# ETH1G_RGMII_RTL8211F.net
KiCad netlist of a schematic drawn in Altium Designer
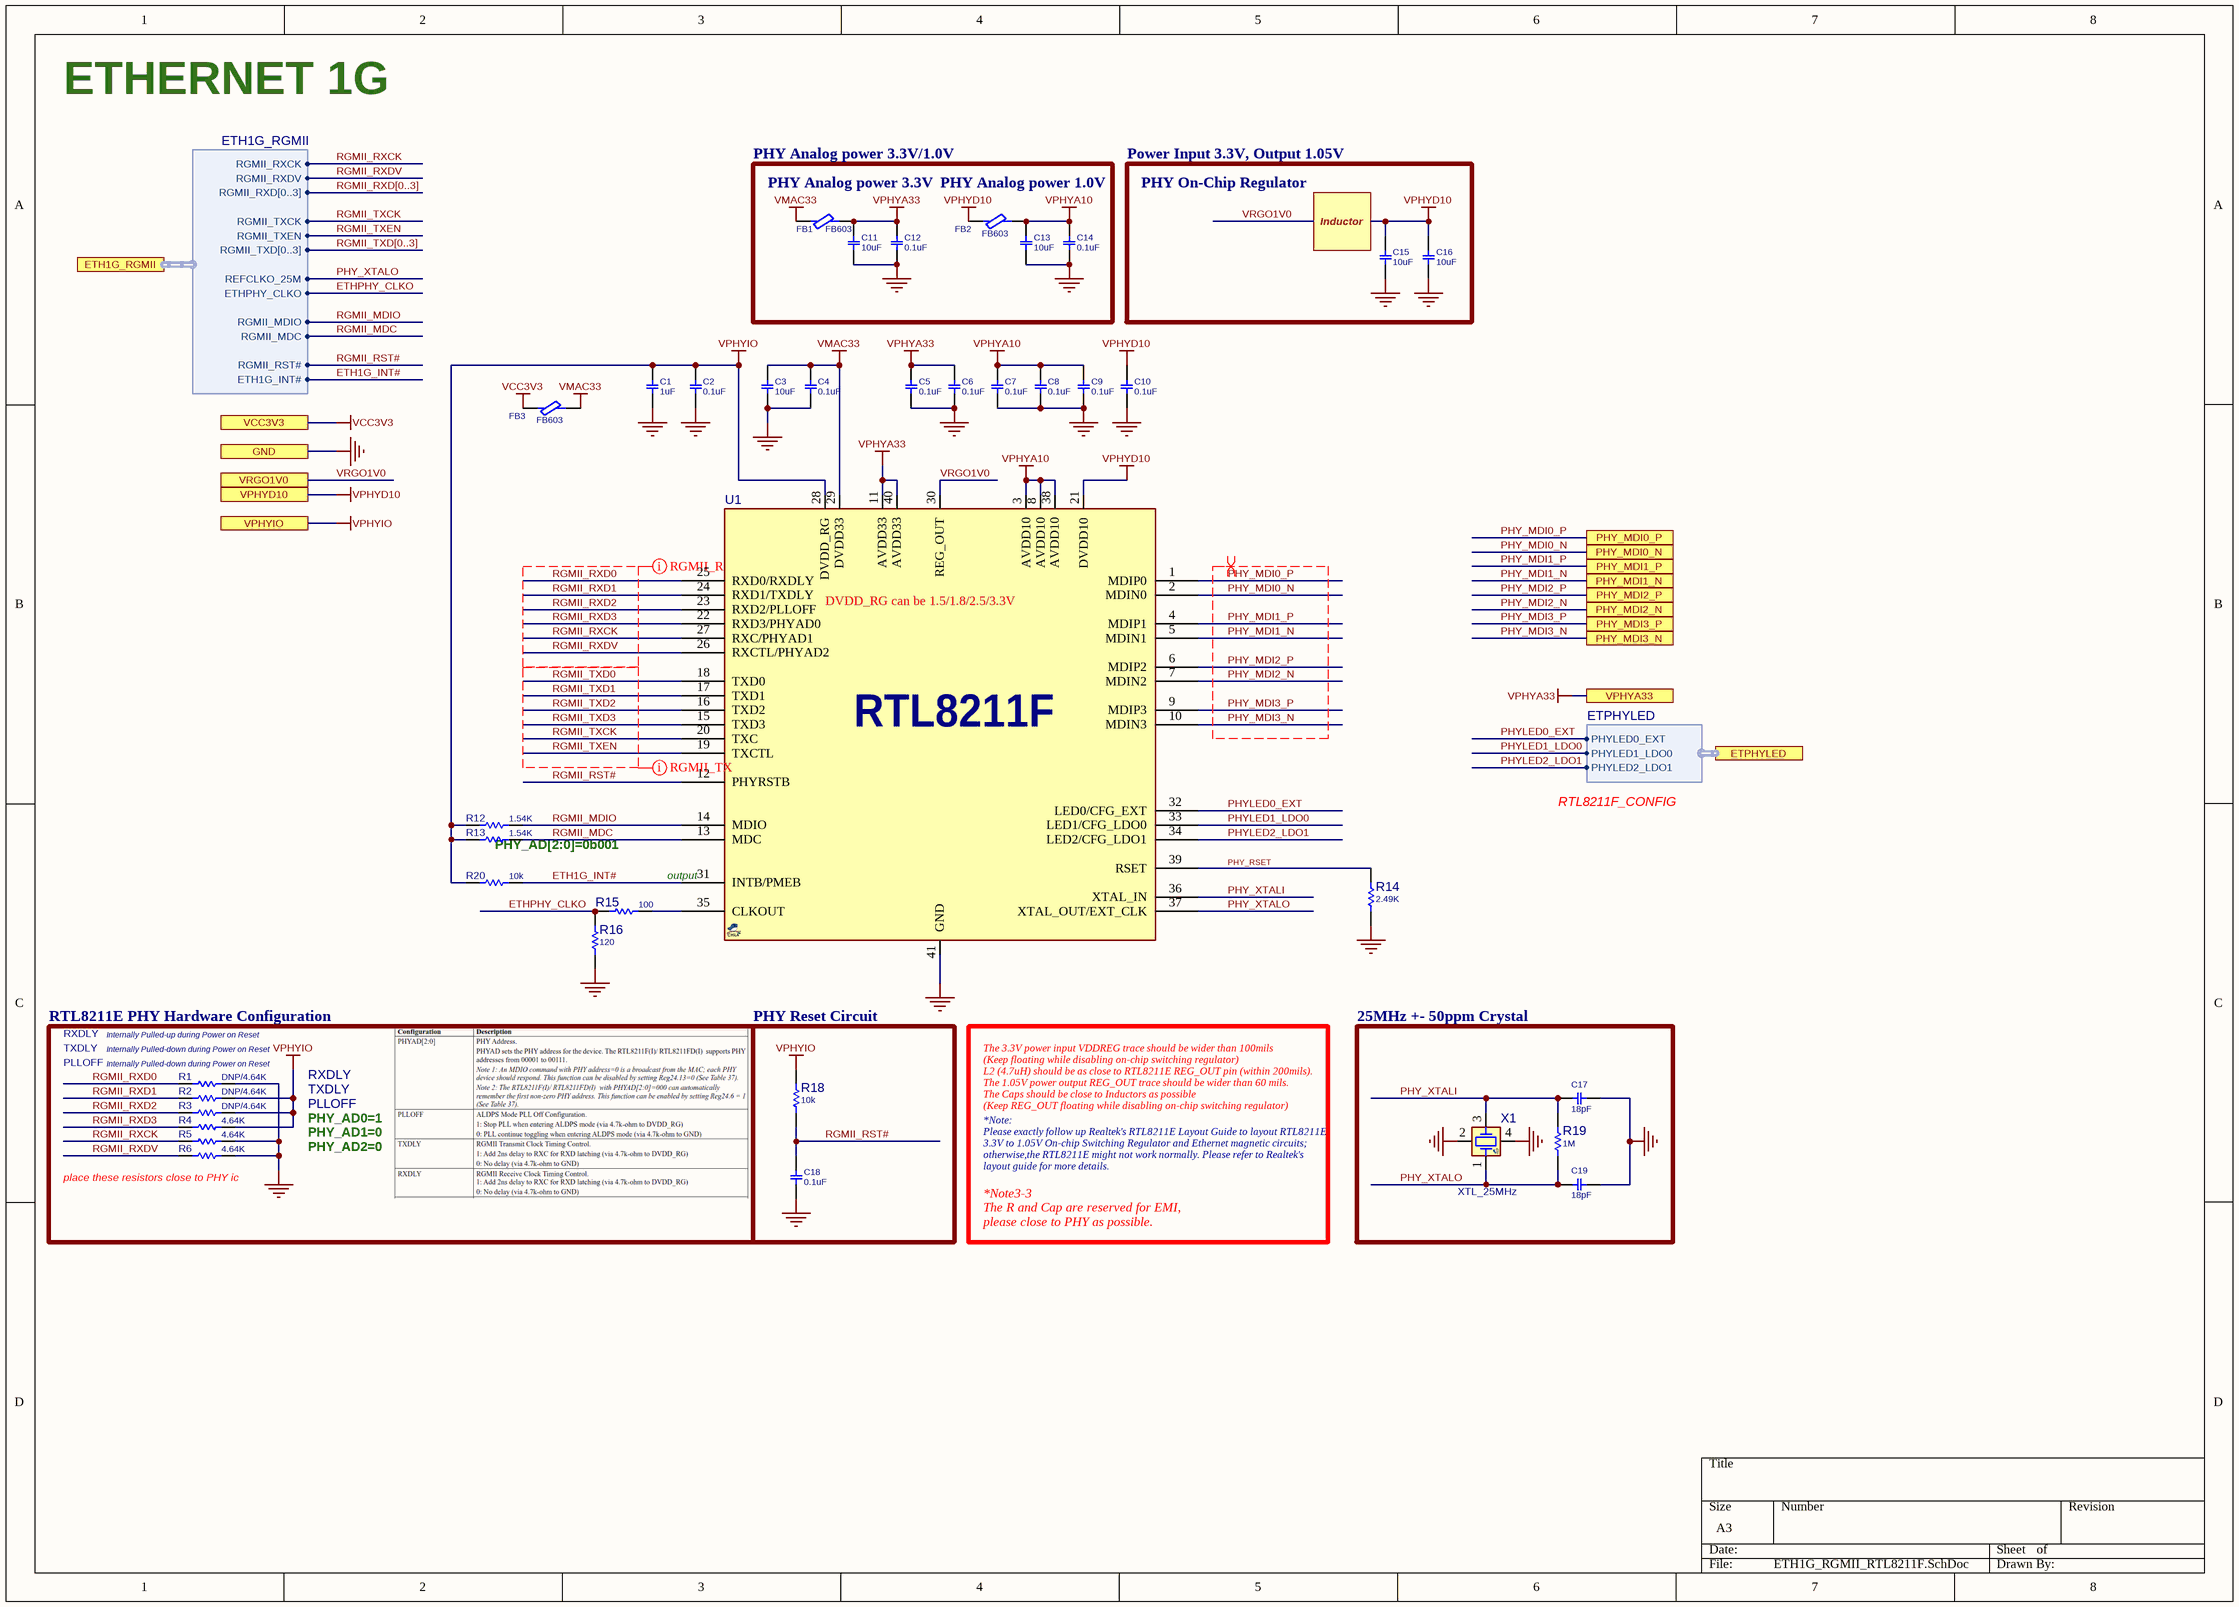
[diagram p0: ETH1G_RGMII_RTL8211F.SchDoc]

(export (version "E")
  (design (tool "Eeschema 10.0.6"))
  (components
    (comp (ref "C1")
      (value "1uF")
      (footprint "C0402")
      (description "CAP, MLCC")
      (fields (field (name "MANF_P#") "CL05A105KO5NNND") (field (name "MANF") "Samsung"))
      (libsource (lib "passive_smd") (part "CAP_SMD_MLCC"))
    )
    (comp (ref "C2")
      (value "0.1uF")
      (footprint "C0402")
      (description "CAP, MLCC")
      (fields (field (name "MANF_P#") "GRM155R61E104") (field (name "MANF") "Murata"))
      (libsource (lib "mlcc_smd_passive") (part "CAP_SMD_MLCC_100n50T"))
    )
    (comp (ref "C3")
      (value "10uF")
      (footprint "C0402")
      (description "CAP, MLCC")
      (fields (field (name "MANF_P#") "CL05A106MP5NUNC") (field (name "MANF") "Samsung"))
      (libsource (lib "mlcc_smd_passive") (part "CAP_SMD_MLCC_100n50T"))
    )
    (comp (ref "C4")
      (value "0.1uF")
      (footprint "C0402")
      (description "CAP, MLCC")
      (fields (field (name "MANF_P#") "GRM155R61E104") (field (name "MANF") "Murata"))
      (libsource (lib "mlcc_smd_passive") (part "CAP_SMD_MLCC_100n50T"))
    )
    (comp (ref "C5")
      (value "0.1uF")
      (footprint "C0402")
      (description "CAP, MLCC")
      (fields (field (name "MANF_P#") "GRM155R61E104") (field (name "MANF") "Murata"))
      (libsource (lib "mlcc_smd_passive") (part "CAP_SMD_MLCC_100n50T"))
    )
    (comp (ref "C6")
      (value "0.1uF")
      (footprint "C0402")
      (description "CAP, MLCC")
      (fields (field (name "MANF_P#") "GRM155R61E104") (field (name "MANF") "Murata"))
      (libsource (lib "mlcc_smd_passive") (part "CAP_SMD_MLCC_100n50T"))
    )
    (comp (ref "C7")
      (value "0.1uF")
      (footprint "C0402")
      (description "CAP, MLCC")
      (fields (field (name "MANF_P#") "GRM155R61E104") (field (name "MANF") "Murata"))
      (libsource (lib "mlcc_smd_passive") (part "CAP_SMD_MLCC_100n50T"))
    )
    (comp (ref "C8")
      (value "0.1uF")
      (footprint "C0402")
      (description "CAP, MLCC")
      (fields (field (name "MANF_P#") "GRM155R61E104") (field (name "MANF") "Murata"))
      (libsource (lib "mlcc_smd_passive") (part "CAP_SMD_MLCC_100n50T"))
    )
    (comp (ref "C9")
      (value "0.1uF")
      (footprint "C0402")
      (description "CAP, MLCC")
      (fields (field (name "MANF_P#") "GRM155R61E104") (field (name "MANF") "Murata"))
      (libsource (lib "mlcc_smd_passive") (part "CAP_SMD_MLCC_100n50T"))
    )
    (comp (ref "C10")
      (value "0.1uF")
      (footprint "C0402")
      (description "CAP, MLCC")
      (fields (field (name "MANF_P#") "GRM155R61E104") (field (name "MANF") "Murata"))
      (libsource (lib "mlcc_smd_passive") (part "CAP_SMD_MLCC_100n50T"))
    )
    (comp (ref "C11")
      (value "10uF")
      (footprint "C0402")
      (description "CAP, MLCC")
      (fields (field (name "MANF_P#") "CL05A106MP5NUNC") (field (name "MANF") "Samsung"))
      (libsource (lib "mlcc_smd_passive") (part "CAP_SMD_MLCC_100n50T"))
    )
    (comp (ref "C12")
      (value "0.1uF")
      (footprint "C0402")
      (description "CAP, MLCC")
      (fields (field (name "MANF_P#") "GRM155R61E104") (field (name "MANF") "Murata"))
      (libsource (lib "mlcc_smd_passive") (part "CAP_SMD_MLCC_100n50T"))
    )
    (comp (ref "C13")
      (value "10uF")
      (footprint "C0402")
      (description "CAP, MLCC")
      (fields (field (name "MANF_P#") "CL05A106MP5NUNC") (field (name "MANF") "Samsung"))
      (libsource (lib "mlcc_smd_passive") (part "CAP_SMD_MLCC_100n50T"))
    )
    (comp (ref "C14")
      (value "0.1uF")
      (footprint "C0402")
      (description "CAP, MLCC")
      (fields (field (name "MANF_P#") "GRM155R61E104") (field (name "MANF") "Murata"))
      (libsource (lib "mlcc_smd_passive") (part "CAP_SMD_MLCC_100n50T"))
    )
    (comp (ref "C15")
      (value "10uF")
      (footprint "C0402")
      (description "CAP, MLCC")
      (fields (field (name "MANF_P#") "CL05A106MP5NUNC") (field (name "MANF") "Samsung"))
      (libsource (lib "mlcc_smd_passive") (part "CAP_SMD_MLCC_100n50T"))
    )
    (comp (ref "C16")
      (value "10uF")
      (footprint "C0402")
      (description "CAP, MLCC")
      (fields (field (name "MANF_P#") "CL05A106MP5NUNC") (field (name "MANF") "Samsung"))
      (libsource (lib "mlcc_smd_passive") (part "CAP_SMD_MLCC_100n50T"))
    )
    (comp (ref "C17")
      (value "18pF")
      (footprint "C0402")
      (description "CAP, MLCC")
      (fields (field (name "MANF_P#") "CC0402JRNPO9BN180") (field (name "MANF") "Yageo"))
      (libsource (lib "mlcc_smd_passive") (part "CAP_SMD_MLCC_100n50T"))
    )
    (comp (ref "C18")
      (value "0.1uF")
      (footprint "C0402")
      (description "CAP, MLCC")
      (fields (field (name "MANF_P#") "GRM155R61E104") (field (name "MANF") "Murata"))
      (libsource (lib "mlcc_smd_passive") (part "CAP_SMD_MLCC_100n50T"))
    )
    (comp (ref "C19")
      (value "18pF")
      (footprint "C0402")
      (description "CAP, MLCC")
      (fields (field (name "MANF_P#") "CC0402JRNPO9BN180") (field (name "MANF") "Yageo"))
      (libsource (lib "mlcc_smd_passive") (part "CAP_SMD_MLCC_100n50T"))
    )
    (comp (ref "FB1")
      (value "FB603")
      (footprint "L0603")
      (description "FERRITE_Bead, 0603, 0.8A, 300mOhm, 1000@100MHz")
      (fields (field (name "MANF") "MURATA") (field (name "MANF_P#") "BLM18KG601SN1D"))
      (libsource (lib "emi_filter") (part "FBEAD_SMD_MPZ1608S102"))
    )
    (comp (ref "FB2")
      (value "FB603")
      (footprint "L0603")
      (description "FERRITE_Bead, 0603, 0.8A, 300mOhm, 1000@100MHz")
      (fields (field (name "MANF") "MURATA") (field (name "MANF_P#") "BLM18KG601SN1D"))
      (libsource (lib "emi_filter") (part "FBEAD_SMD_MPZ1608S102"))
    )
    (comp (ref "FB3")
      (value "FB603")
      (footprint "L0603")
      (description "FERRITE_Bead, 0603, 0.8A, 300mOhm, 1000@100MHz")
      (fields (field (name "MANF") "MURATA") (field (name "MANF_P#") "BLM18KG601SN1D"))
      (libsource (lib "emi_filter") (part "FBEAD_SMD_MPZ1608S102"))
    )
    (comp (ref "R1")
      (value "DNP/4.64K")
      (footprint "R0402")
      (description "RESISTOR, SMD")
      (libsource (lib "passive_res_smd") (part "RES_SMD_10K_0402"))
    )
    (comp (ref "R2")
      (value "DNP/4.64K")
      (footprint "R0402")
      (description "RESISTOR, SMD")
      (libsource (lib "passive_res_smd") (part "RES_SMD_10K_0402"))
    )
    (comp (ref "R3")
      (value "DNP/4.64K")
      (footprint "R0402")
      (description "RESISTOR, SMD")
      (libsource (lib "passive_res_smd") (part "RES_SMD_10K_0402"))
    )
    (comp (ref "R4")
      (value "4.64K")
      (footprint "R0402")
      (description "RESISTOR, SMD")
      (libsource (lib "passive_res_smd") (part "RES_SMD_10K_0402"))
    )
    (comp (ref "R5")
      (value "4.64K")
      (footprint "R0402")
      (description "RESISTOR, SMD")
      (libsource (lib "passive_res_smd") (part "RES_SMD_10K_0402"))
    )
    (comp (ref "R6")
      (value "4.64K")
      (footprint "R0402")
      (description "RESISTOR, SMD")
      (libsource (lib "passive_res_smd") (part "RES_SMD_10K_0402"))
    )
    (comp (ref "R12")
      (value "1.54K")
      (footprint "R0402")
      (description "RESISTOR, SMD")
      (libsource (lib "passive_res_smd") (part "RES_SMD_10K_0402"))
    )
    (comp (ref "R13")
      (value "1.54K")
      (footprint "R0402")
      (description "RESISTOR, SMD")
      (libsource (lib "passive_res_smd") (part "RES_SMD_10K_0402"))
    )
    (comp (ref "R14")
      (value "2.49K")
      (footprint "R0402")
      (description "RESISTOR, SMD")
      (libsource (lib "passive_res_smd") (part "RES_SMD_10K_0402"))
    )
    (comp (ref "R15")
      (value "100")
      (footprint "R0402")
      (description "RESISTOR, SMD")
      (libsource (lib "passive_res_smd") (part "RES_SMD_10K_0402"))
    )
    (comp (ref "R16")
      (value "120")
      (footprint "R0402")
      (description "RESISTOR, SMD")
      (libsource (lib "passive_res_smd") (part "RES_SMD_10K_0402"))
    )
    (comp (ref "R18")
      (value "10k")
      (footprint "R0402")
      (description "RESISTOR, SMD")
      (libsource (lib "passive_res_smd") (part "RES_SMD_10K_0402"))
    )
    (comp (ref "R19")
      (value "1M")
      (footprint "R0402")
      (description "RESISTOR, SMD")
      (libsource (lib "passive_res_smd") (part "RES_SMD_10K_0402"))
    )
    (comp (ref "R20")
      (value "10k")
      (footprint "R0402")
      (description "RESISTOR, SMD")
      (libsource (lib "passive_res_smd") (part "RES_SMD_10K_0402"))
    )
    (comp (ref "U1")
      (value "RTL8211F")
      (footprint "QFN40_40T")
      (description "Ethernet Transceiver, 10/100/1000, RGMII")
      (fields (field (name "MANF_P#") "RTL8211FI-CG") (field (name "MANF") "Realtek"))
      (libsource (lib "ethernet") (part "RTL8211F_QFN40"))
    )
    (comp (ref "X1")
      (value "XTL_25MHz")
      (footprint "XTL_4_2016")
      (description "CRYSTAL 25.00 MHZ 6pF, 10PPM")
      (fields (field (name "MANF") "Murata") (field (name "MANF_P#") "XRCGB25M000F1H00R0"))
      (libsource (lib "crystal") (part "XTL_4_25MHz_3225"))
    )
  )
  (nets
    (net (code "3") (name "/ETH1G_INT#") (class "Default")
      (node (ref "R20") (pin "2") (pinfunction "2_2") (pintype "passive"))
      (node (ref "U1") (pin "31") (pinfunction "INTB/PMEB_31") (pintype "passive"))
    )
    (net (code "5") (name "/ETHPHY_CLKO") (class "Default")
      (node (ref "R15") (pin "1") (pinfunction "1_1") (pintype "passive"))
      (node (ref "R16") (pin "2") (pinfunction "2_2") (pintype "passive"))
    )
    (net (code "6") (name "/PHYLED0_EXT") (class "Default")
      (node (ref "U1") (pin "32") (pinfunction "LED0/CFG_EXT_32") (pintype "passive"))
    )
    (net (code "7") (name "/PHYLED1_LDO0") (class "Default")
      (node (ref "U1") (pin "33") (pinfunction "LED1/CFG_LDO0_33") (pintype "passive"))
    )
    (net (code "8") (name "/PHYLED2_LDO1") (class "Default")
      (node (ref "U1") (pin "34") (pinfunction "LED2/CFG_LDO1_34") (pintype "passive"))
    )
    (net (code "9") (name "/PHY_MDI0_N") (class "Default")
      (node (ref "U1") (pin "2") (pinfunction "MDIN0_2") (pintype "passive"))
    )
    (net (code "10") (name "/PHY_MDI0_P") (class "Default")
      (node (ref "U1") (pin "1") (pinfunction "MDIP0_1") (pintype "passive"))
    )
    (net (code "11") (name "/PHY_MDI1_N") (class "Default")
      (node (ref "U1") (pin "5") (pinfunction "MDIN1_5") (pintype "passive"))
    )
    (net (code "12") (name "/PHY_MDI1_P") (class "Default")
      (node (ref "U1") (pin "4") (pinfunction "MDIP1_4") (pintype "passive"))
    )
    (net (code "13") (name "/PHY_MDI2_N") (class "Default")
      (node (ref "U1") (pin "7") (pinfunction "MDIN2_7") (pintype "passive"))
    )
    (net (code "14") (name "/PHY_MDI2_P") (class "Default")
      (node (ref "U1") (pin "6") (pinfunction "MDIP2_6") (pintype "passive"))
    )
    (net (code "15") (name "/PHY_MDI3_N") (class "Default")
      (node (ref "U1") (pin "10") (pinfunction "MDIN3_10") (pintype "passive"))
    )
    (net (code "16") (name "/PHY_MDI3_P") (class "Default")
      (node (ref "U1") (pin "9") (pinfunction "MDIP3_9") (pintype "passive"))
    )
    (net (code "17") (name "/PHY_RSET") (class "Default")
      (node (ref "R14") (pin "2") (pinfunction "2_2") (pintype "passive"))
      (node (ref "U1") (pin "39") (pinfunction "RSET_39") (pintype "passive"))
    )
    (net (code "18") (name "/PHY_XTALI") (class "Default")
      (node (ref "C17") (pin "1") (pinfunction "1_1") (pintype "passive"))
      (node (ref "R19") (pin "2") (pinfunction "2_2") (pintype "passive"))
      (node (ref "U1") (pin "36") (pinfunction "XTAL_IN_36") (pintype "passive"))
      (node (ref "X1") (pin "3") (pinfunction "XB_3") (pintype "passive"))
    )
    (net (code "19") (name "/PHY_XTALO") (class "Default")
      (node (ref "C19") (pin "1") (pinfunction "1_1") (pintype "passive"))
      (node (ref "R19") (pin "1") (pinfunction "1_1") (pintype "passive"))
      (node (ref "U1") (pin "37") (pinfunction "XTAL_OUT/EXT_CLK_37") (pintype "passive"))
      (node (ref "X1") (pin "1") (pinfunction "XA_1") (pintype "passive"))
    )
    (net (code "20") (name "/RGMII_MDC") (class "Default")
      (node (ref "R13") (pin "2") (pinfunction "2_2") (pintype "passive"))
      (node (ref "U1") (pin "13") (pinfunction "MDC_13") (pintype "passive"))
    )
    (net (code "21") (name "/RGMII_MDIO") (class "Default")
      (node (ref "R12") (pin "2") (pinfunction "2_2") (pintype "passive"))
      (node (ref "U1") (pin "14") (pinfunction "MDIO_14") (pintype "passive"))
    )
    (net (code "22") (name "/RGMII_RST#") (class "Default")
      (node (ref "C18") (pin "2") (pinfunction "2_2") (pintype "passive"))
      (node (ref "R18") (pin "2") (pinfunction "2_2") (pintype "passive"))
      (node (ref "U1") (pin "12") (pinfunction "PHYRSTB_12") (pintype "passive"))
    )
    (net (code "23") (name "/RGMII_RXCK") (class "Default")
      (node (ref "R5") (pin "1") (pinfunction "1_1") (pintype "passive"))
      (node (ref "U1") (pin "27") (pinfunction "RXC/PHYAD1_27") (pintype "passive"))
    )
    (net (code "24") (name "/RGMII_RXD0") (class "Default")
      (node (ref "R1") (pin "1") (pinfunction "1_1") (pintype "passive"))
      (node (ref "U1") (pin "25") (pinfunction "RXD0/RXDLY_25") (pintype "passive"))
    )
    (net (code "25") (name "/RGMII_RXD1") (class "Default")
      (node (ref "R2") (pin "1") (pinfunction "1_1") (pintype "passive"))
      (node (ref "U1") (pin "24") (pinfunction "RXD1/TXDLY_24") (pintype "passive"))
    )
    (net (code "26") (name "/RGMII_RXD2") (class "Default")
      (node (ref "R3") (pin "1") (pinfunction "1_1") (pintype "passive"))
      (node (ref "U1") (pin "23") (pinfunction "RXD2/PLLOFF_23") (pintype "passive"))
    )
    (net (code "27") (name "/RGMII_RXD3") (class "Default")
      (node (ref "R4") (pin "1") (pinfunction "1_1") (pintype "passive"))
      (node (ref "U1") (pin "22") (pinfunction "RXD3/PHYAD0_22") (pintype "passive"))
    )
    (net (code "28") (name "/RGMII_RXDV") (class "Default")
      (node (ref "R6") (pin "1") (pinfunction "1_1") (pintype "passive"))
      (node (ref "U1") (pin "26") (pinfunction "RXCTL/PHYAD2_26") (pintype "passive"))
    )
    (net (code "29") (name "/RGMII_TXCK") (class "Default")
      (node (ref "U1") (pin "20") (pinfunction "TXC_20") (pintype "passive"))
    )
    (net (code "30") (name "/RGMII_TXD0") (class "Default")
      (node (ref "U1") (pin "18") (pinfunction "TXD0_18") (pintype "passive"))
    )
    (net (code "31") (name "/RGMII_TXD1") (class "Default")
      (node (ref "U1") (pin "17") (pinfunction "TXD1_17") (pintype "passive"))
    )
    (net (code "32") (name "/RGMII_TXD2") (class "Default")
      (node (ref "U1") (pin "16") (pinfunction "TXD2_16") (pintype "passive"))
    )
    (net (code "33") (name "/RGMII_TXD3") (class "Default")
      (node (ref "U1") (pin "15") (pinfunction "TXD3_15") (pintype "passive"))
    )
    (net (code "35") (name "/RGMII_TXEN") (class "Default")
      (node (ref "U1") (pin "19") (pinfunction "TXCTL_19") (pintype "passive"))
    )
    (net (code "36") (name "/VRGO1V0") (class "Default")
      (node (ref "U1") (pin "30") (pinfunction "REG_OUT_30") (pintype "passive"))
    )
    (net (code "39") (name "GND") (class "Default")
      (node (ref "C1") (pin "1") (pinfunction "1_1") (pintype "passive"))
      (node (ref "C10") (pin "2") (pinfunction "2_2") (pintype "passive"))
      (node (ref "C11") (pin "2") (pinfunction "2_2") (pintype "passive"))
      (node (ref "C12") (pin "2") (pinfunction "2_2") (pintype "passive"))
      (node (ref "C13") (pin "2") (pinfunction "2_2") (pintype "passive"))
      (node (ref "C14") (pin "2") (pinfunction "2_2") (pintype "passive"))
      (node (ref "C15") (pin "2") (pinfunction "2_2") (pintype "passive"))
      (node (ref "C16") (pin "2") (pinfunction "2_2") (pintype "passive"))
      (node (ref "C17") (pin "2") (pinfunction "2_2") (pintype "passive"))
      (node (ref "C18") (pin "1") (pinfunction "1_1") (pintype "passive"))
      (node (ref "C19") (pin "2") (pinfunction "2_2") (pintype "passive"))
      (node (ref "C2") (pin "2") (pinfunction "2_2") (pintype "passive"))
      (node (ref "C3") (pin "2") (pinfunction "2_2") (pintype "passive"))
      (node (ref "C4") (pin "2") (pinfunction "2_2") (pintype "passive"))
      (node (ref "C5") (pin "2") (pinfunction "2_2") (pintype "passive"))
      (node (ref "C6") (pin "2") (pinfunction "2_2") (pintype "passive"))
      (node (ref "C7") (pin "2") (pinfunction "2_2") (pintype "passive"))
      (node (ref "C8") (pin "2") (pinfunction "2_2") (pintype "passive"))
      (node (ref "C9") (pin "2") (pinfunction "2_2") (pintype "passive"))
      (node (ref "R1") (pin "2") (pinfunction "2_2") (pintype "passive"))
      (node (ref "R14") (pin "1") (pinfunction "1_1") (pintype "passive"))
      (node (ref "R16") (pin "1") (pinfunction "1_1") (pintype "passive"))
      (node (ref "R5") (pin "2") (pinfunction "2_2") (pintype "passive"))
      (node (ref "R6") (pin "2") (pinfunction "2_2") (pintype "passive"))
      (node (ref "U1") (pin "41") (pinfunction "GND_41") (pintype "passive"))
      (node (ref "X1") (pin "2") (pinfunction "GND1_2") (pintype "passive"))
      (node (ref "X1") (pin "4") (pinfunction "GND2_4") (pintype "passive"))
    )
    (net (code "40") (name "Net-(U1-CLKOUT)") (class "Default")
      (node (ref "R15") (pin "2") (pinfunction "2_2") (pintype "passive"))
      (node (ref "U1") (pin "35") (pinfunction "CLKOUT_35") (pintype "passive"))
    )
    (net (code "41") (name "VCC3V3") (class "Default")
      (node (ref "FB3") (pin "1") (pinfunction "1_1") (pintype "passive"))
    )
    (net (code "42") (name "VMAC33") (class "Default")
      (node (ref "C3") (pin "1") (pinfunction "1_1") (pintype "passive"))
      (node (ref "C4") (pin "1") (pinfunction "1_1") (pintype "passive"))
      (node (ref "FB1") (pin "1") (pinfunction "1_1") (pintype "passive"))
      (node (ref "FB3") (pin "2") (pinfunction "2_2") (pintype "passive"))
      (node (ref "U1") (pin "29") (pinfunction "DVDD33_29") (pintype "passive"))
    )
    (net (code "43") (name "VPHYA10") (class "Default")
      (node (ref "C13") (pin "1") (pinfunction "1_1") (pintype "passive"))
      (node (ref "C14") (pin "1") (pinfunction "1_1") (pintype "passive"))
      (node (ref "C7") (pin "1") (pinfunction "1_1") (pintype "passive"))
      (node (ref "C8") (pin "1") (pinfunction "1_1") (pintype "passive"))
      (node (ref "C9") (pin "1") (pinfunction "1_1") (pintype "passive"))
      (node (ref "FB2") (pin "2") (pinfunction "2_2") (pintype "passive"))
      (node (ref "U1") (pin "3") (pinfunction "AVDD10_3") (pintype "passive"))
      (node (ref "U1") (pin "38") (pinfunction "AVDD10_38") (pintype "passive"))
      (node (ref "U1") (pin "8") (pinfunction "AVDD10_8") (pintype "passive"))
    )
    (net (code "44") (name "VPHYA33") (class "Default")
      (node (ref "C11") (pin "1") (pinfunction "1_1") (pintype "passive"))
      (node (ref "C12") (pin "1") (pinfunction "1_1") (pintype "passive"))
      (node (ref "C5") (pin "1") (pinfunction "1_1") (pintype "passive"))
      (node (ref "C6") (pin "1") (pinfunction "1_1") (pintype "passive"))
      (node (ref "FB1") (pin "2") (pinfunction "2_2") (pintype "passive"))
      (node (ref "U1") (pin "11") (pinfunction "AVDD33_11") (pintype "passive"))
      (node (ref "U1") (pin "40") (pinfunction "AVDD33_40") (pintype "passive"))
    )
    (net (code "45") (name "VPHYD10") (class "Default")
      (node (ref "C10") (pin "1") (pinfunction "1_1") (pintype "passive"))
      (node (ref "C15") (pin "1") (pinfunction "1_1") (pintype "passive"))
      (node (ref "C16") (pin "1") (pinfunction "1_1") (pintype "passive"))
      (node (ref "FB2") (pin "1") (pinfunction "1_1") (pintype "passive"))
      (node (ref "U1") (pin "21") (pinfunction "DVDD10_21") (pintype "passive"))
    )
    (net (code "46") (name "VPHYIO") (class "Default")
      (node (ref "C1") (pin "2") (pinfunction "2_2") (pintype "passive"))
      (node (ref "C2") (pin "1") (pinfunction "1_1") (pintype "passive"))
      (node (ref "R12") (pin "1") (pinfunction "1_1") (pintype "passive"))
      (node (ref "R13") (pin "1") (pinfunction "1_1") (pintype "passive"))
      (node (ref "R18") (pin "1") (pinfunction "1_1") (pintype "passive"))
      (node (ref "R2") (pin "2") (pinfunction "2_2") (pintype "passive"))
      (node (ref "R20") (pin "1") (pinfunction "1_1") (pintype "passive"))
      (node (ref "R3") (pin "2") (pinfunction "2_2") (pintype "passive"))
      (node (ref "R4") (pin "2") (pinfunction "2_2") (pintype "passive"))
      (node (ref "U1") (pin "28") (pinfunction "DVDD_RG_28") (pintype "passive"))
    )
  )
)
